# typewriter_shift.net
KiCad netlist of a schematic drawn in EAGLE
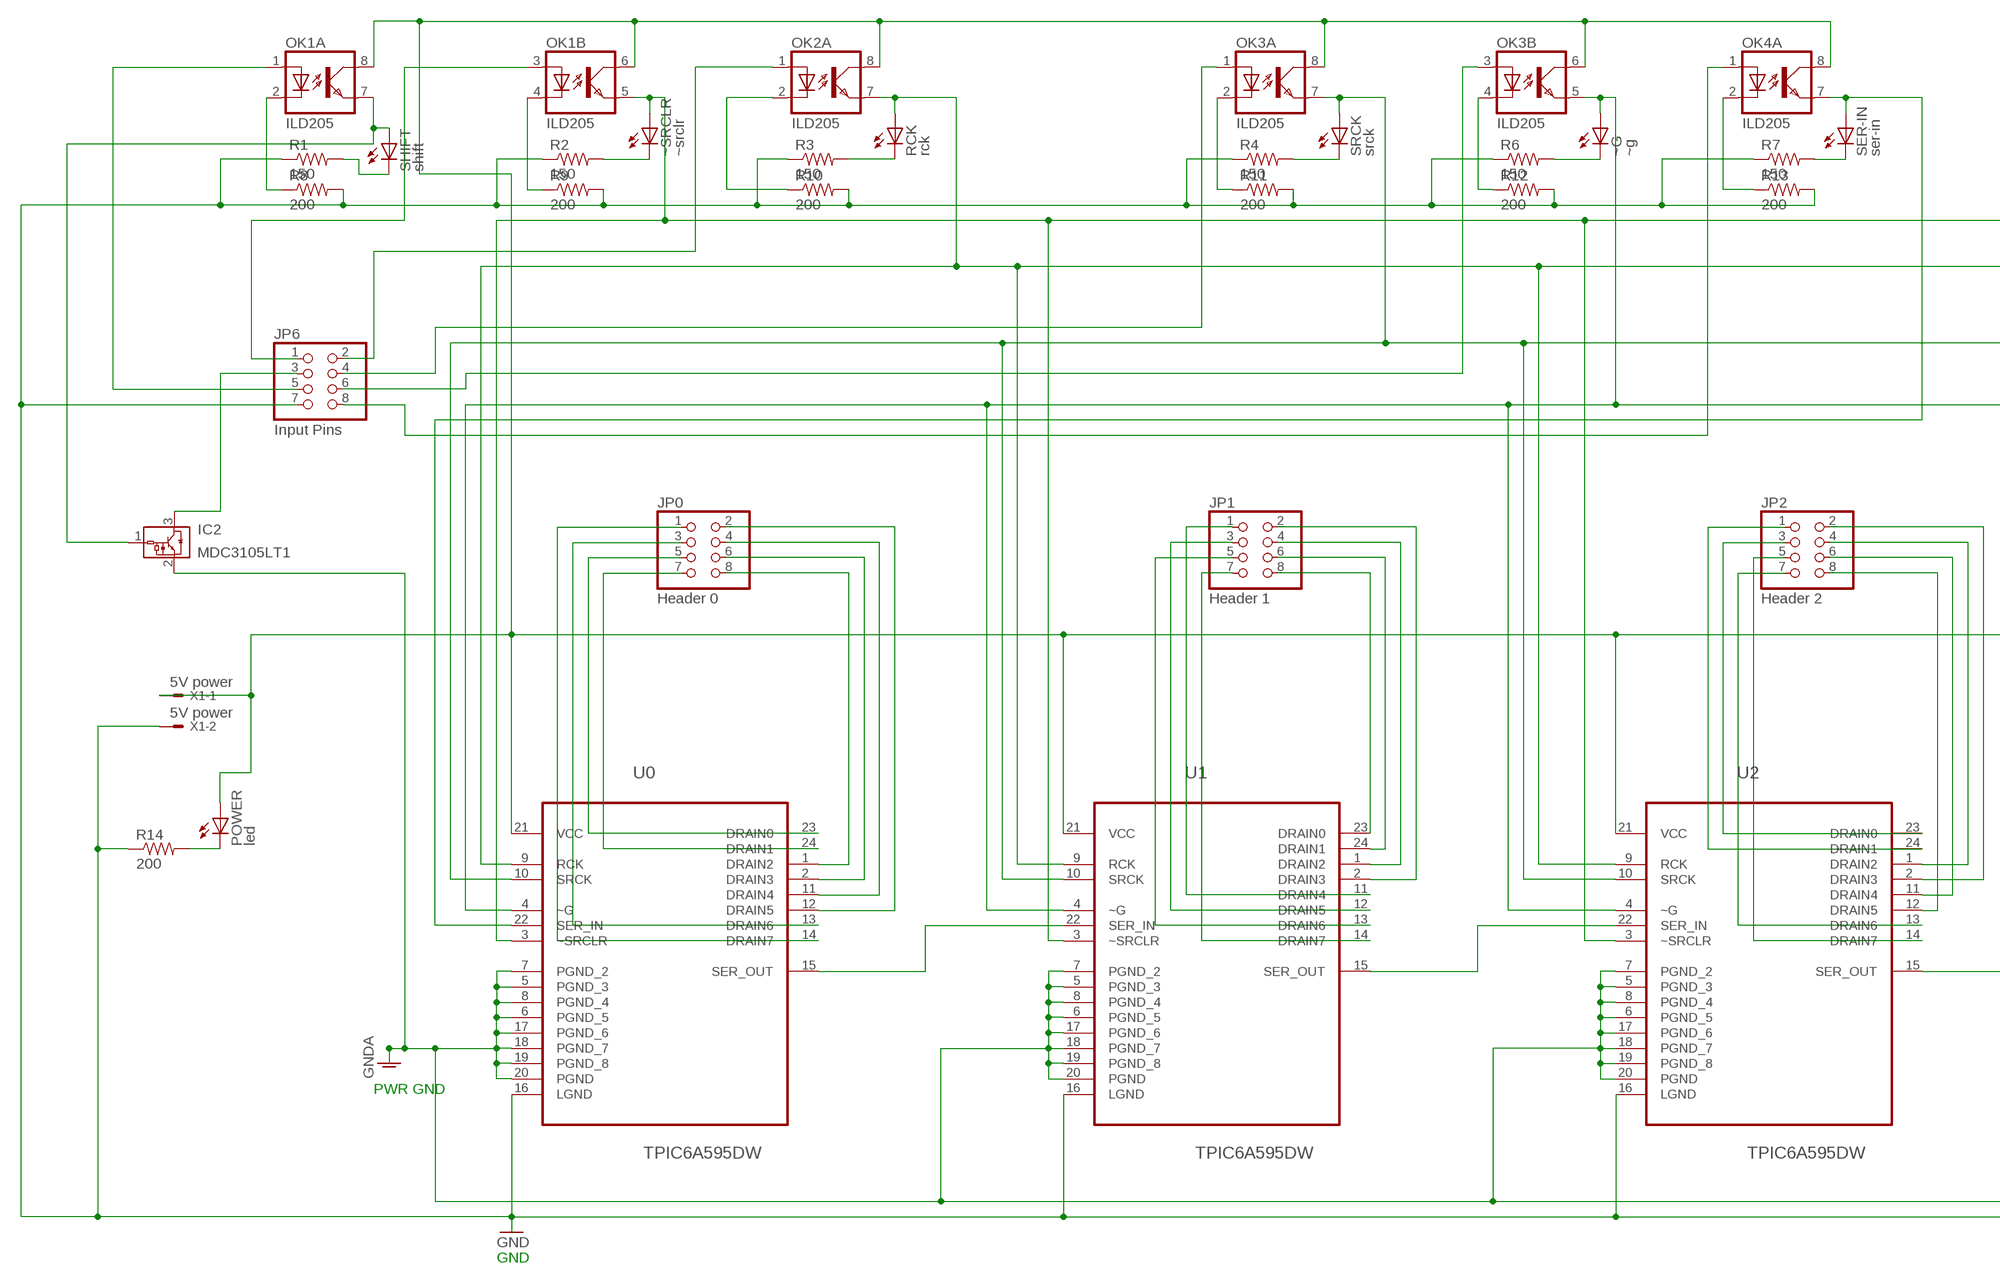
[diagram p0: schematic, sheet 1, part 1 of 2]
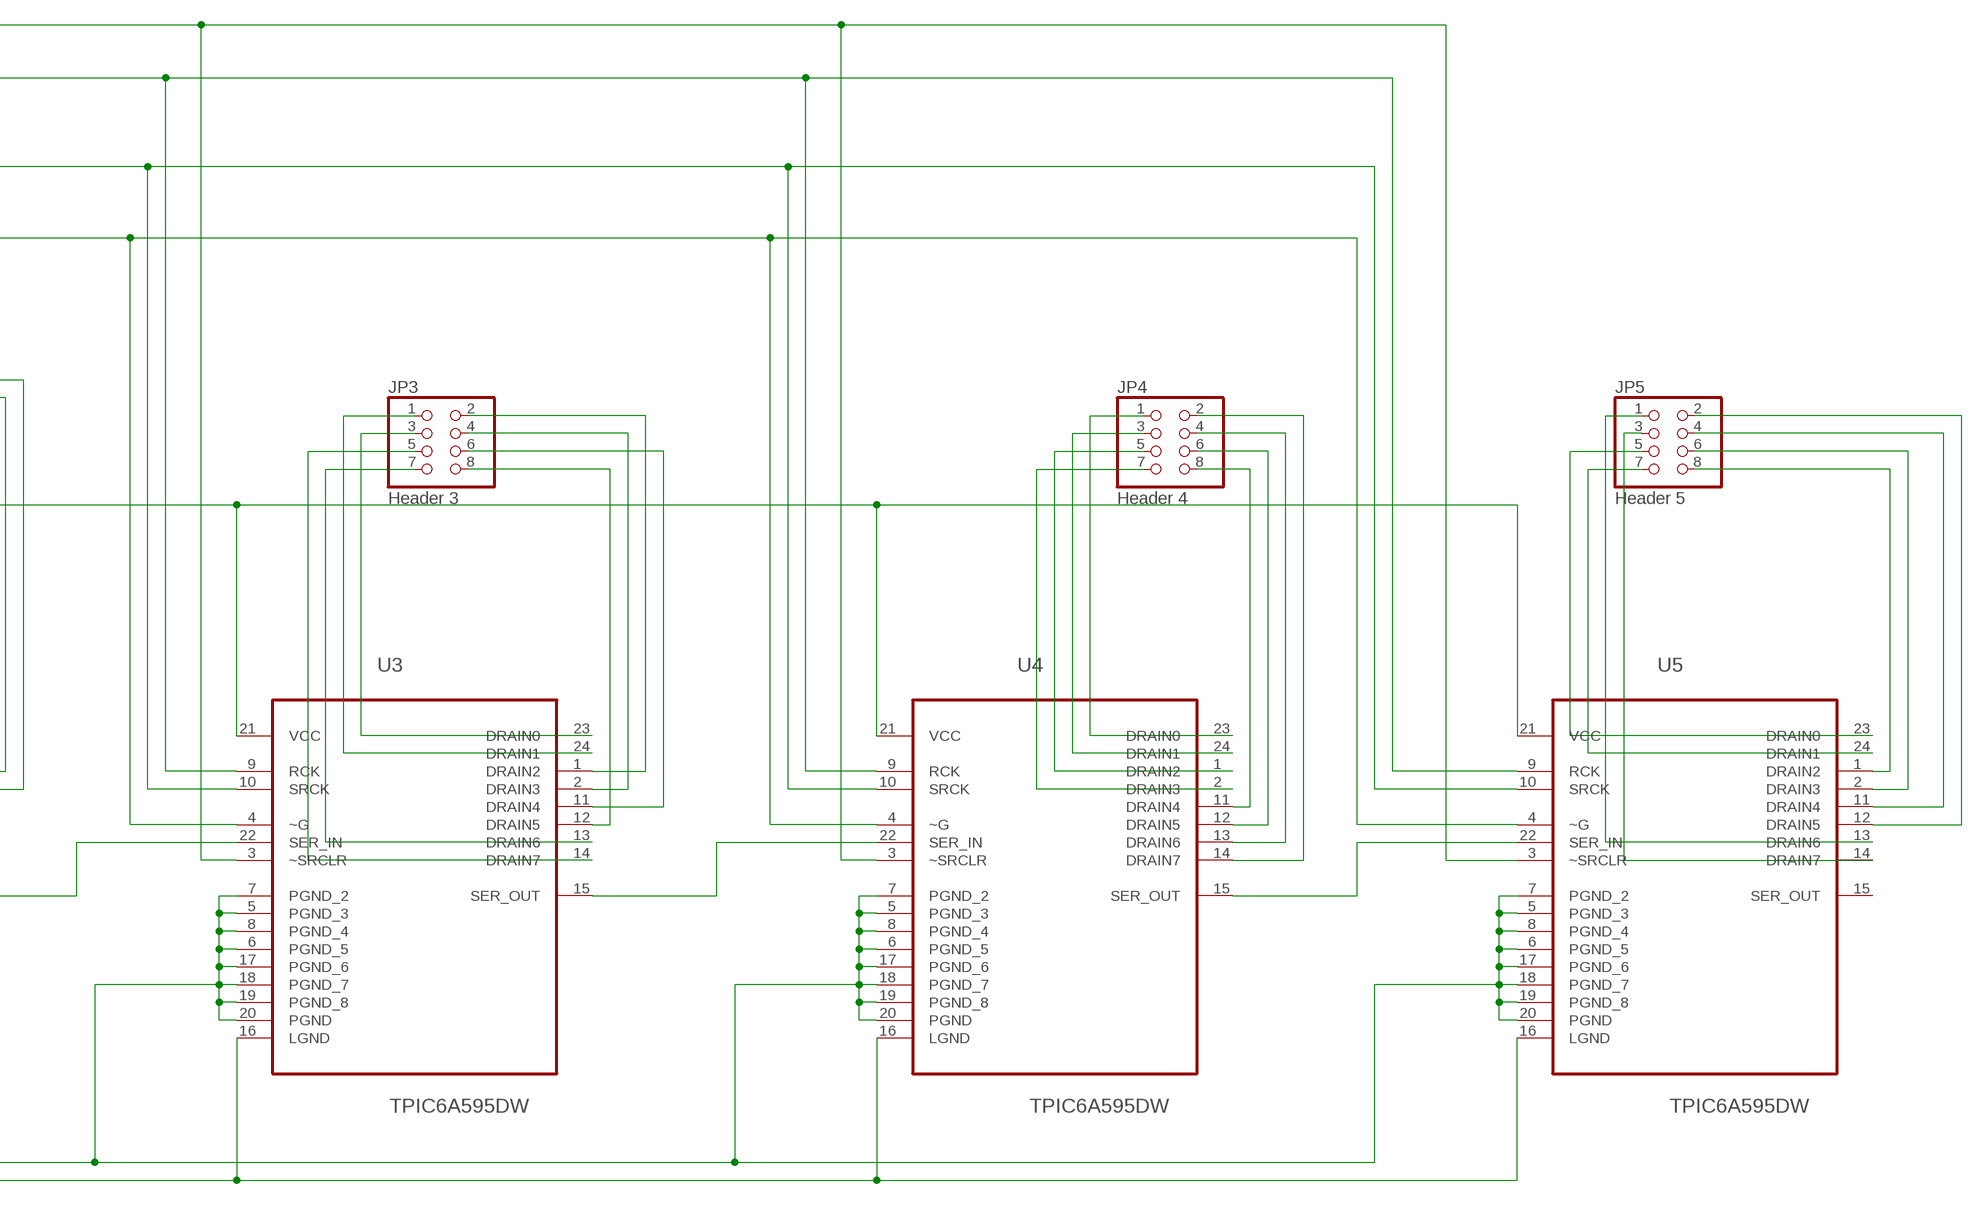
[diagram p1: schematic, sheet 1, part 2 of 2]

(export (version "E")
  (design (tool "Eeschema 10.0.6"))
  (components
    (comp (ref "IC2")
      (value "MDC3105LT1")
      (footprint "eagle-import:SOT23")
      (fields (field (name "MF") "ON SEMICONDUCTOR"))
      (libsource (lib "eagle-import") (part "MDC3105LT1"))
    )
    (comp (ref "JP0")
      (value "Header 0")
      (footprint "eagle-import:2X04_90")
      (libsource (lib "eagle-import") (part "PINHD-2X4/90"))
    )
    (comp (ref "JP1")
      (value "Header 1")
      (footprint "eagle-import:2X04_90")
      (libsource (lib "eagle-import") (part "PINHD-2X4/90"))
    )
    (comp (ref "JP2")
      (value "Header 2")
      (footprint "eagle-import:2X04_90")
      (libsource (lib "eagle-import") (part "PINHD-2X4/90"))
    )
    (comp (ref "JP3")
      (value "Header 3")
      (footprint "eagle-import:2X04_90")
      (libsource (lib "eagle-import") (part "PINHD-2X4/90"))
    )
    (comp (ref "JP4")
      (value "Header 4")
      (footprint "eagle-import:2X04_90")
      (libsource (lib "eagle-import") (part "PINHD-2X4/90"))
    )
    (comp (ref "JP5")
      (value "Header 5")
      (footprint "eagle-import:2X04_90")
      (libsource (lib "eagle-import") (part "PINHD-2X4/90"))
    )
    (comp (ref "JP6")
      (value "Input Pins")
      (footprint "eagle-import:2X04_90")
      (libsource (lib "eagle-import") (part "PINHD-2X4/90"))
    )
    (comp (ref "OK1")
      (value "ILD205")
      (footprint "eagle-import:SOIC08")
      (fields (field (name "MF") "VISHAY/TELEFUNKEN") (field (name "MPN") "ILD205T"))
      (libsource (lib "eagle-import") (part "ILD205"))
    )
    (comp (ref "OK2")
      (value "ILD205")
      (footprint "eagle-import:SOIC08")
      (fields (field (name "MF") "VISHAY/TELEFUNKEN") (field (name "MPN") "ILD205T"))
      (libsource (lib "eagle-import") (part "ILD205"))
    )
    (comp (ref "OK3")
      (value "ILD205")
      (footprint "eagle-import:SOIC08")
      (fields (field (name "MF") "VISHAY/TELEFUNKEN") (field (name "MPN") "ILD205T"))
      (libsource (lib "eagle-import") (part "ILD205"))
    )
    (comp (ref "OK4")
      (value "ILD205")
      (footprint "eagle-import:SOIC08")
      (fields (field (name "MF") "VISHAY/TELEFUNKEN") (field (name "MPN") "ILD205T"))
      (libsource (lib "eagle-import") (part "ILD205"))
    )
    (comp (ref "POWER")
      (value "led")
      (footprint "eagle-import:SML1206")
      (libsource (lib "eagle-import") (part "LEDSML1206"))
    )
    (comp (ref "R1")
      (value "150")
      (footprint "eagle-import:R1206")
      (libsource (lib "eagle-import") (part "R-US_R1206"))
    )
    (comp (ref "R2")
      (value "150")
      (footprint "eagle-import:R1206")
      (libsource (lib "eagle-import") (part "R-US_R1206"))
    )
    (comp (ref "R3")
      (value "150")
      (footprint "eagle-import:R1206")
      (libsource (lib "eagle-import") (part "R-US_R1206"))
    )
    (comp (ref "R4")
      (value "150")
      (footprint "eagle-import:R1206")
      (libsource (lib "eagle-import") (part "R-US_R1206"))
    )
    (comp (ref "R6")
      (value "150")
      (footprint "eagle-import:R1206")
      (libsource (lib "eagle-import") (part "R-US_R1206"))
    )
    (comp (ref "R7")
      (value "150")
      (footprint "eagle-import:R1206")
      (libsource (lib "eagle-import") (part "R-US_R1206"))
    )
    (comp (ref "R8")
      (value "200")
      (footprint "eagle-import:R1206")
      (libsource (lib "eagle-import") (part "R-US_R1206"))
    )
    (comp (ref "R9")
      (value "200")
      (footprint "eagle-import:R1206")
      (libsource (lib "eagle-import") (part "R-US_R1206"))
    )
    (comp (ref "R10")
      (value "200")
      (footprint "eagle-import:R1206")
      (libsource (lib "eagle-import") (part "R-US_R1206"))
    )
    (comp (ref "R11")
      (value "200")
      (footprint "eagle-import:R1206")
      (libsource (lib "eagle-import") (part "R-US_R1206"))
    )
    (comp (ref "R12")
      (value "200")
      (footprint "eagle-import:R1206")
      (libsource (lib "eagle-import") (part "R-US_R1206"))
    )
    (comp (ref "R13")
      (value "200")
      (footprint "eagle-import:R1206")
      (libsource (lib "eagle-import") (part "R-US_R1206"))
    )
    (comp (ref "R14")
      (value "200")
      (footprint "eagle-import:R1206")
      (libsource (lib "eagle-import") (part "R-US_R1206"))
    )
    (comp (ref "RCK")
      (value "rck")
      (footprint "eagle-import:SML1206")
      (libsource (lib "eagle-import") (part "LEDSML1206"))
    )
    (comp (ref "SER-IN")
      (value "ser-in")
      (footprint "eagle-import:SML1206")
      (libsource (lib "eagle-import") (part "LEDSML1206"))
    )
    (comp (ref "SHIFT")
      (value "shift")
      (footprint "eagle-import:SML1206")
      (libsource (lib "eagle-import") (part "LEDSML1206"))
    )
    (comp (ref "SRCK")
      (value "srck")
      (footprint "eagle-import:SML1206")
      (libsource (lib "eagle-import") (part "LEDSML1206"))
    )
    (comp (ref "U0")
      (value "TPIC6A595DW")
      (footprint "eagle-import:SOIC127P1030X265-24N")
      (libsource (lib "eagle-import") (part "TPIC6A595DW"))
    )
    (comp (ref "U1")
      (value "TPIC6A595DW")
      (footprint "eagle-import:SOIC127P1030X265-24N")
      (libsource (lib "eagle-import") (part "TPIC6A595DW"))
    )
    (comp (ref "U2")
      (value "TPIC6A595DW")
      (footprint "eagle-import:SOIC127P1030X265-24N")
      (libsource (lib "eagle-import") (part "TPIC6A595DW"))
    )
    (comp (ref "U3")
      (value "TPIC6A595DW")
      (footprint "eagle-import:SOIC127P1030X265-24N")
      (libsource (lib "eagle-import") (part "TPIC6A595DW"))
    )
    (comp (ref "U4")
      (value "TPIC6A595DW")
      (footprint "eagle-import:SOIC127P1030X265-24N")
      (libsource (lib "eagle-import") (part "TPIC6A595DW"))
    )
    (comp (ref "U5")
      (value "TPIC6A595DW")
      (footprint "eagle-import:SOIC127P1030X265-24N")
      (libsource (lib "eagle-import") (part "TPIC6A595DW"))
    )
    (comp (ref "X1")
      (value "5V power")
      (footprint "eagle-import:KK-156-2")
      (libsource (lib "eagle-import") (part "KK-156-2"))
    )
    (comp (ref "~G")
      (value "~g")
      (footprint "eagle-import:SML1206")
      (libsource (lib "eagle-import") (part "LEDSML1206"))
    )
    (comp (ref "~SRCLR")
      (value "~srclr")
      (footprint "eagle-import:SML1206")
      (libsource (lib "eagle-import") (part "LEDSML1206"))
    )
  )
  (nets
    (net (code "1") (name "GND") (class "Default")
      (node (ref "JP6") (pin "7") (pinfunction "7_7") (pintype "passive"))
      (node (ref "R1") (pin "1") (pinfunction "1_1") (pintype "passive"))
      (node (ref "R10") (pin "2") (pinfunction "2_2") (pintype "passive"))
      (node (ref "R11") (pin "2") (pinfunction "2_2") (pintype "passive"))
      (node (ref "R12") (pin "2") (pinfunction "2_2") (pintype "passive"))
      (node (ref "R13") (pin "2") (pinfunction "2_2") (pintype "passive"))
      (node (ref "R14") (pin "1") (pinfunction "1_1") (pintype "passive"))
      (node (ref "R2") (pin "1") (pinfunction "1_1") (pintype "passive"))
      (node (ref "R3") (pin "1") (pinfunction "1_1") (pintype "passive"))
      (node (ref "R4") (pin "1") (pinfunction "1_1") (pintype "passive"))
      (node (ref "R6") (pin "1") (pinfunction "1_1") (pintype "passive"))
      (node (ref "R7") (pin "1") (pinfunction "1_1") (pintype "passive"))
      (node (ref "R8") (pin "2") (pinfunction "2_2") (pintype "passive"))
      (node (ref "R9") (pin "2") (pinfunction "2_2") (pintype "passive"))
      (node (ref "U0") (pin "16") (pinfunction "LGND_16") (pintype "passive"))
      (node (ref "U1") (pin "16") (pinfunction "LGND_16") (pintype "passive"))
      (node (ref "U2") (pin "16") (pinfunction "LGND_16") (pintype "passive"))
      (node (ref "U3") (pin "16") (pinfunction "LGND_16") (pintype "passive"))
      (node (ref "U4") (pin "16") (pinfunction "LGND_16") (pintype "passive"))
      (node (ref "U5") (pin "16") (pinfunction "LGND_16") (pintype "passive"))
      (node (ref "X1") (pin "2") (pinfunction "S_2") (pintype "passive"))
    )
    (net (code "2") (name "GNDA") (class "Default")
      (node (ref "IC2") (pin "2") (pinfunction "GND_2") (pintype "passive"))
      (node (ref "U0") (pin "17") (pinfunction "PGND_6_17") (pintype "passive"))
      (node (ref "U0") (pin "18") (pinfunction "PGND_7_18") (pintype "passive"))
      (node (ref "U0") (pin "19") (pinfunction "PGND_8_19") (pintype "passive"))
      (node (ref "U0") (pin "20") (pinfunction "PGND_20") (pintype "passive"))
      (node (ref "U0") (pin "5") (pinfunction "PGND_3_5") (pintype "passive"))
      (node (ref "U0") (pin "6") (pinfunction "PGND_5_6") (pintype "passive"))
      (node (ref "U0") (pin "7") (pinfunction "PGND_2_7") (pintype "passive"))
      (node (ref "U0") (pin "8") (pinfunction "PGND_4_8") (pintype "passive"))
      (node (ref "U1") (pin "17") (pinfunction "PGND_6_17") (pintype "passive"))
      (node (ref "U1") (pin "18") (pinfunction "PGND_7_18") (pintype "passive"))
      (node (ref "U1") (pin "19") (pinfunction "PGND_8_19") (pintype "passive"))
      (node (ref "U1") (pin "20") (pinfunction "PGND_20") (pintype "passive"))
      (node (ref "U1") (pin "5") (pinfunction "PGND_3_5") (pintype "passive"))
      (node (ref "U1") (pin "6") (pinfunction "PGND_5_6") (pintype "passive"))
      (node (ref "U1") (pin "7") (pinfunction "PGND_2_7") (pintype "passive"))
      (node (ref "U1") (pin "8") (pinfunction "PGND_4_8") (pintype "passive"))
      (node (ref "U2") (pin "17") (pinfunction "PGND_6_17") (pintype "passive"))
      (node (ref "U2") (pin "18") (pinfunction "PGND_7_18") (pintype "passive"))
      (node (ref "U2") (pin "19") (pinfunction "PGND_8_19") (pintype "passive"))
      (node (ref "U2") (pin "20") (pinfunction "PGND_20") (pintype "passive"))
      (node (ref "U2") (pin "5") (pinfunction "PGND_3_5") (pintype "passive"))
      (node (ref "U2") (pin "6") (pinfunction "PGND_5_6") (pintype "passive"))
      (node (ref "U2") (pin "7") (pinfunction "PGND_2_7") (pintype "passive"))
      (node (ref "U2") (pin "8") (pinfunction "PGND_4_8") (pintype "passive"))
      (node (ref "U3") (pin "17") (pinfunction "PGND_6_17") (pintype "passive"))
      (node (ref "U3") (pin "18") (pinfunction "PGND_7_18") (pintype "passive"))
      (node (ref "U3") (pin "19") (pinfunction "PGND_8_19") (pintype "passive"))
      (node (ref "U3") (pin "20") (pinfunction "PGND_20") (pintype "passive"))
      (node (ref "U3") (pin "5") (pinfunction "PGND_3_5") (pintype "passive"))
      (node (ref "U3") (pin "6") (pinfunction "PGND_5_6") (pintype "passive"))
      (node (ref "U3") (pin "7") (pinfunction "PGND_2_7") (pintype "passive"))
      (node (ref "U3") (pin "8") (pinfunction "PGND_4_8") (pintype "passive"))
      (node (ref "U4") (pin "17") (pinfunction "PGND_6_17") (pintype "passive"))
      (node (ref "U4") (pin "18") (pinfunction "PGND_7_18") (pintype "passive"))
      (node (ref "U4") (pin "19") (pinfunction "PGND_8_19") (pintype "passive"))
      (node (ref "U4") (pin "20") (pinfunction "PGND_20") (pintype "passive"))
      (node (ref "U4") (pin "5") (pinfunction "PGND_3_5") (pintype "passive"))
      (node (ref "U4") (pin "6") (pinfunction "PGND_5_6") (pintype "passive"))
      (node (ref "U4") (pin "7") (pinfunction "PGND_2_7") (pintype "passive"))
      (node (ref "U4") (pin "8") (pinfunction "PGND_4_8") (pintype "passive"))
      (node (ref "U5") (pin "17") (pinfunction "PGND_6_17") (pintype "passive"))
      (node (ref "U5") (pin "18") (pinfunction "PGND_7_18") (pintype "passive"))
      (node (ref "U5") (pin "19") (pinfunction "PGND_8_19") (pintype "passive"))
      (node (ref "U5") (pin "20") (pinfunction "PGND_20") (pintype "passive"))
      (node (ref "U5") (pin "5") (pinfunction "PGND_3_5") (pintype "passive"))
      (node (ref "U5") (pin "6") (pinfunction "PGND_5_6") (pintype "passive"))
      (node (ref "U5") (pin "7") (pinfunction "PGND_2_7") (pintype "passive"))
      (node (ref "U5") (pin "8") (pinfunction "PGND_4_8") (pintype "passive"))
    )
    (net (code "3") (name "Net-(IC2-VIN)") (class "Default")
      (node (ref "IC2") (pin "1") (pinfunction "VIN_1") (pintype "passive"))
      (node (ref "OK1") (pin "7") (pinfunction "EMIT_7") (pintype "passive"))
      (node (ref "SHIFT") (pin "A") (pinfunction "A_A") (pintype "passive"))
    )
    (net (code "4") (name "Net-(IC2-VOUT)") (class "Default")
      (node (ref "IC2") (pin "3") (pinfunction "VOUT_3") (pintype "passive"))
      (node (ref "JP6") (pin "3") (pinfunction "3_3") (pintype "passive"))
    )
    (net (code "5") (name "Net-(OK1A-A)") (class "Default")
      (node (ref "JP6") (pin "5") (pinfunction "5_5") (pintype "passive"))
      (node (ref "OK1") (pin "1") (pinfunction "A_1") (pintype "passive"))
    )
    (net (code "6") (name "Net-(OK1A-C)") (class "Default")
      (node (ref "OK1") (pin "2") (pinfunction "C_2") (pintype "passive"))
      (node (ref "R8") (pin "1") (pinfunction "1_1") (pintype "passive"))
    )
    (net (code "7") (name "Net-(OK1A-COL)") (class "Default")
      (node (ref "OK1") (pin "6") (pinfunction "COL_6") (pintype "passive"))
      (node (ref "OK1") (pin "8") (pinfunction "COL_8") (pintype "passive"))
      (node (ref "OK2") (pin "8") (pinfunction "COL_8") (pintype "passive"))
      (node (ref "OK3") (pin "6") (pinfunction "COL_6") (pintype "passive"))
      (node (ref "OK3") (pin "8") (pinfunction "COL_8") (pintype "passive"))
      (node (ref "OK4") (pin "8") (pinfunction "COL_8") (pintype "passive"))
      (node (ref "POWER") (pin "A") (pinfunction "A_A") (pintype "passive"))
      (node (ref "U0") (pin "21") (pinfunction "VCC_21") (pintype "power_in"))
      (node (ref "U1") (pin "21") (pinfunction "VCC_21") (pintype "power_in"))
      (node (ref "U2") (pin "21") (pinfunction "VCC_21") (pintype "power_in"))
      (node (ref "U3") (pin "21") (pinfunction "VCC_21") (pintype "power_in"))
      (node (ref "U4") (pin "21") (pinfunction "VCC_21") (pintype "power_in"))
      (node (ref "U5") (pin "21") (pinfunction "VCC_21") (pintype "power_in"))
      (node (ref "X1") (pin "1") (pinfunction "S_1") (pintype "passive"))
    )
    (net (code "8") (name "Net-(OK1B-A)") (class "Default")
      (node (ref "JP6") (pin "1") (pinfunction "1_1") (pintype "passive"))
      (node (ref "OK1") (pin "3") (pinfunction "A_3") (pintype "passive"))
    )
    (net (code "9") (name "Net-(OK1B-C)") (class "Default")
      (node (ref "OK1") (pin "4") (pinfunction "C_4") (pintype "passive"))
      (node (ref "R9") (pin "1") (pinfunction "1_1") (pintype "passive"))
    )
    (net (code "10") (name "Net-(OK1B-EMIT)") (class "Default")
      (node (ref "OK1") (pin "5") (pinfunction "EMIT_5") (pintype "passive"))
      (node (ref "U0") (pin "3") (pinfunction "~{SRCLR}_3") (pintype "input"))
      (node (ref "U1") (pin "3") (pinfunction "~{SRCLR}_3") (pintype "input"))
      (node (ref "U2") (pin "3") (pinfunction "~{SRCLR}_3") (pintype "input"))
      (node (ref "U3") (pin "3") (pinfunction "~{SRCLR}_3") (pintype "input"))
      (node (ref "U4") (pin "3") (pinfunction "~{SRCLR}_3") (pintype "input"))
      (node (ref "U5") (pin "3") (pinfunction "~{SRCLR}_3") (pintype "input"))
      (node (ref "~SRCLR") (pin "A") (pinfunction "A_A") (pintype "passive"))
    )
    (net (code "11") (name "Net-(OK2A-A)") (class "Default")
      (node (ref "JP6") (pin "2") (pinfunction "2_2") (pintype "passive"))
      (node (ref "OK2") (pin "1") (pinfunction "A_1") (pintype "passive"))
    )
    (net (code "12") (name "Net-(OK2A-C)") (class "Default")
      (node (ref "OK2") (pin "2") (pinfunction "C_2") (pintype "passive"))
      (node (ref "R10") (pin "1") (pinfunction "1_1") (pintype "passive"))
    )
    (net (code "13") (name "Net-(OK2A-EMIT)") (class "Default")
      (node (ref "OK2") (pin "7") (pinfunction "EMIT_7") (pintype "passive"))
      (node (ref "RCK") (pin "A") (pinfunction "A_A") (pintype "passive"))
      (node (ref "U0") (pin "9") (pinfunction "RCK_9") (pintype "input"))
      (node (ref "U1") (pin "9") (pinfunction "RCK_9") (pintype "input"))
      (node (ref "U2") (pin "9") (pinfunction "RCK_9") (pintype "input"))
      (node (ref "U3") (pin "9") (pinfunction "RCK_9") (pintype "input"))
      (node (ref "U4") (pin "9") (pinfunction "RCK_9") (pintype "input"))
      (node (ref "U5") (pin "9") (pinfunction "RCK_9") (pintype "input"))
    )
    (net (code "14") (name "Net-(OK3A-A)") (class "Default")
      (node (ref "JP6") (pin "4") (pinfunction "4_4") (pintype "passive"))
      (node (ref "OK3") (pin "1") (pinfunction "A_1") (pintype "passive"))
    )
    (net (code "15") (name "Net-(OK3A-C)") (class "Default")
      (node (ref "OK3") (pin "2") (pinfunction "C_2") (pintype "passive"))
      (node (ref "R11") (pin "1") (pinfunction "1_1") (pintype "passive"))
    )
    (net (code "16") (name "Net-(OK3A-EMIT)") (class "Default")
      (node (ref "OK3") (pin "7") (pinfunction "EMIT_7") (pintype "passive"))
      (node (ref "SRCK") (pin "A") (pinfunction "A_A") (pintype "passive"))
      (node (ref "U0") (pin "10") (pinfunction "SRCK_10") (pintype "input"))
      (node (ref "U1") (pin "10") (pinfunction "SRCK_10") (pintype "input"))
      (node (ref "U2") (pin "10") (pinfunction "SRCK_10") (pintype "input"))
      (node (ref "U3") (pin "10") (pinfunction "SRCK_10") (pintype "input"))
      (node (ref "U4") (pin "10") (pinfunction "SRCK_10") (pintype "input"))
      (node (ref "U5") (pin "10") (pinfunction "SRCK_10") (pintype "input"))
    )
    (net (code "17") (name "Net-(OK3B-A)") (class "Default")
      (node (ref "JP6") (pin "6") (pinfunction "6_6") (pintype "passive"))
      (node (ref "OK3") (pin "3") (pinfunction "A_3") (pintype "passive"))
    )
    (net (code "18") (name "Net-(OK3B-C)") (class "Default")
      (node (ref "OK3") (pin "4") (pinfunction "C_4") (pintype "passive"))
      (node (ref "R12") (pin "1") (pinfunction "1_1") (pintype "passive"))
    )
    (net (code "19") (name "Net-(OK3B-EMIT)") (class "Default")
      (node (ref "OK3") (pin "5") (pinfunction "EMIT_5") (pintype "passive"))
      (node (ref "U0") (pin "4") (pinfunction "~{G}_4") (pintype "input"))
      (node (ref "U1") (pin "4") (pinfunction "~{G}_4") (pintype "input"))
      (node (ref "U2") (pin "4") (pinfunction "~{G}_4") (pintype "input"))
      (node (ref "U3") (pin "4") (pinfunction "~{G}_4") (pintype "input"))
      (node (ref "U4") (pin "4") (pinfunction "~{G}_4") (pintype "input"))
      (node (ref "U5") (pin "4") (pinfunction "~{G}_4") (pintype "input"))
      (node (ref "~G") (pin "A") (pinfunction "A_A") (pintype "passive"))
    )
    (net (code "20") (name "Net-(OK4A-A)") (class "Default")
      (node (ref "JP6") (pin "8") (pinfunction "8_8") (pintype "passive"))
      (node (ref "OK4") (pin "1") (pinfunction "A_1") (pintype "passive"))
    )
    (net (code "21") (name "Net-(OK4A-C)") (class "Default")
      (node (ref "OK4") (pin "2") (pinfunction "C_2") (pintype "passive"))
      (node (ref "R13") (pin "1") (pinfunction "1_1") (pintype "passive"))
    )
    (net (code "22") (name "Net-(OK4A-EMIT)") (class "Default")
      (node (ref "OK4") (pin "7") (pinfunction "EMIT_7") (pintype "passive"))
      (node (ref "SER-IN") (pin "A") (pinfunction "A_A") (pintype "passive"))
      (node (ref "U0") (pin "22") (pinfunction "SER_IN_22") (pintype "input"))
    )
    (net (code "23") (name "Net-(POWER-PadC)") (class "Default")
      (node (ref "POWER") (pin "C") (pinfunction "C_C") (pintype "passive"))
      (node (ref "R14") (pin "2") (pinfunction "2_2") (pintype "passive"))
    )
    (net (code "24") (name "Net-(R1-Pad2)") (class "Default")
      (node (ref "R1") (pin "2") (pinfunction "2_2") (pintype "passive"))
      (node (ref "SHIFT") (pin "C") (pinfunction "C_C") (pintype "passive"))
    )
    (net (code "25") (name "Net-(R2-Pad2)") (class "Default")
      (node (ref "R2") (pin "2") (pinfunction "2_2") (pintype "passive"))
      (node (ref "~SRCLR") (pin "C") (pinfunction "C_C") (pintype "passive"))
    )
    (net (code "26") (name "Net-(R3-Pad2)") (class "Default")
      (node (ref "R3") (pin "2") (pinfunction "2_2") (pintype "passive"))
      (node (ref "RCK") (pin "C") (pinfunction "C_C") (pintype "passive"))
    )
    (net (code "27") (name "Net-(R4-Pad2)") (class "Default")
      (node (ref "R4") (pin "2") (pinfunction "2_2") (pintype "passive"))
      (node (ref "SRCK") (pin "C") (pinfunction "C_C") (pintype "passive"))
    )
    (net (code "28") (name "Net-(R6-Pad2)") (class "Default")
      (node (ref "R6") (pin "2") (pinfunction "2_2") (pintype "passive"))
      (node (ref "~G") (pin "C") (pinfunction "C_C") (pintype "passive"))
    )
    (net (code "29") (name "Net-(R7-Pad2)") (class "Default")
      (node (ref "R7") (pin "2") (pinfunction "2_2") (pintype "passive"))
      (node (ref "SER-IN") (pin "C") (pinfunction "C_C") (pintype "passive"))
    )
    (net (code "30") (name "Net-(U0-DRAIN0)") (class "Default")
      (node (ref "JP0") (pin "5") (pinfunction "5_5") (pintype "passive"))
      (node (ref "U0") (pin "23") (pinfunction "DRAIN0_23") (pintype "output"))
    )
    (net (code "31") (name "Net-(U0-DRAIN1)") (class "Default")
      (node (ref "JP0") (pin "7") (pinfunction "7_7") (pintype "passive"))
      (node (ref "U0") (pin "24") (pinfunction "DRAIN1_24") (pintype "output"))
    )
    (net (code "32") (name "Net-(U0-DRAIN2)") (class "Default")
      (node (ref "JP0") (pin "8") (pinfunction "8_8") (pintype "passive"))
      (node (ref "U0") (pin "1") (pinfunction "DRAIN2_1") (pintype "output"))
    )
    (net (code "33") (name "Net-(U0-DRAIN3)") (class "Default")
      (node (ref "JP0") (pin "6") (pinfunction "6_6") (pintype "passive"))
      (node (ref "U0") (pin "2") (pinfunction "DRAIN3_2") (pintype "output"))
    )
    (net (code "34") (name "Net-(U0-DRAIN4)") (class "Default")
      (node (ref "JP0") (pin "4") (pinfunction "4_4") (pintype "passive"))
      (node (ref "U0") (pin "11") (pinfunction "DRAIN4_11") (pintype "output"))
    )
    (net (code "35") (name "Net-(U0-DRAIN5)") (class "Default")
      (node (ref "JP0") (pin "2") (pinfunction "2_2") (pintype "passive"))
      (node (ref "U0") (pin "12") (pinfunction "DRAIN5_12") (pintype "output"))
    )
    (net (code "36") (name "Net-(U0-DRAIN6)") (class "Default")
      (node (ref "JP0") (pin "3") (pinfunction "3_3") (pintype "passive"))
      (node (ref "U0") (pin "13") (pinfunction "DRAIN6_13") (pintype "output"))
    )
    (net (code "37") (name "Net-(U0-DRAIN7)") (class "Default")
      (node (ref "JP0") (pin "1") (pinfunction "1_1") (pintype "passive"))
      (node (ref "U0") (pin "14") (pinfunction "DRAIN7_14") (pintype "output"))
    )
    (net (code "38") (name "Net-(U0-SER_OUT)") (class "Default")
      (node (ref "U0") (pin "15") (pinfunction "SER_OUT_15") (pintype "output"))
      (node (ref "U1") (pin "22") (pinfunction "SER_IN_22") (pintype "input"))
    )
    (net (code "39") (name "Net-(U1-DRAIN0)") (class "Default")
      (node (ref "JP1") (pin "8") (pinfunction "8_8") (pintype "passive"))
      (node (ref "U1") (pin "23") (pinfunction "DRAIN0_23") (pintype "output"))
    )
    (net (code "40") (name "Net-(U1-DRAIN1)") (class "Default")
      (node (ref "JP1") (pin "6") (pinfunction "6_6") (pintype "passive"))
      (node (ref "U1") (pin "24") (pinfunction "DRAIN1_24") (pintype "output"))
    )
    (net (code "41") (name "Net-(U1-DRAIN2)") (class "Default")
      (node (ref "JP1") (pin "4") (pinfunction "4_4") (pintype "passive"))
      (node (ref "U1") (pin "1") (pinfunction "DRAIN2_1") (pintype "output"))
    )
    (net (code "42") (name "Net-(U1-DRAIN3)") (class "Default")
      (node (ref "JP1") (pin "2") (pinfunction "2_2") (pintype "passive"))
      (node (ref "U1") (pin "2") (pinfunction "DRAIN3_2") (pintype "output"))
    )
    (net (code "43") (name "Net-(U1-DRAIN4)") (class "Default")
      (node (ref "JP1") (pin "1") (pinfunction "1_1") (pintype "passive"))
      (node (ref "U1") (pin "11") (pinfunction "DRAIN4_11") (pintype "output"))
    )
    (net (code "44") (name "Net-(U1-DRAIN5)") (class "Default")
      (node (ref "JP1") (pin "3") (pinfunction "3_3") (pintype "passive"))
      (node (ref "U1") (pin "12") (pinfunction "DRAIN5_12") (pintype "output"))
    )
    (net (code "45") (name "Net-(U1-DRAIN6)") (class "Default")
      (node (ref "JP1") (pin "5") (pinfunction "5_5") (pintype "passive"))
      (node (ref "U1") (pin "13") (pinfunction "DRAIN6_13") (pintype "output"))
    )
    (net (code "46") (name "Net-(U1-DRAIN7)") (class "Default")
      (node (ref "JP1") (pin "7") (pinfunction "7_7") (pintype "passive"))
      (node (ref "U1") (pin "14") (pinfunction "DRAIN7_14") (pintype "output"))
    )
    (net (code "47") (name "Net-(U1-SER_OUT)") (class "Default")
      (node (ref "U1") (pin "15") (pinfunction "SER_OUT_15") (pintype "output"))
      (node (ref "U2") (pin "22") (pinfunction "SER_IN_22") (pintype "input"))
    )
    (net (code "48") (name "Net-(U2-DRAIN0)") (class "Default")
      (node (ref "JP2") (pin "3") (pinfunction "3_3") (pintype "passive"))
      (node (ref "U2") (pin "23") (pinfunction "DRAIN0_23") (pintype "output"))
    )
    (net (code "49") (name "Net-(U2-DRAIN1)") (class "Default")
      (node (ref "JP2") (pin "1") (pinfunction "1_1") (pintype "passive"))
      (node (ref "U2") (pin "24") (pinfunction "DRAIN1_24") (pintype "output"))
    )
    (net (code "50") (name "Net-(U2-DRAIN2)") (class "Default")
      (node (ref "JP2") (pin "4") (pinfunction "4_4") (pintype "passive"))
      (node (ref "U2") (pin "1") (pinfunction "DRAIN2_1") (pintype "output"))
    )
    (net (code "51") (name "Net-(U2-DRAIN3)") (class "Default")
      (node (ref "JP2") (pin "2") (pinfunction "2_2") (pintype "passive"))
      (node (ref "U2") (pin "2") (pinfunction "DRAIN3_2") (pintype "output"))
    )
    (net (code "52") (name "Net-(U2-DRAIN4)") (class "Default")
      (node (ref "JP2") (pin "6") (pinfunction "6_6") (pintype "passive"))
      (node (ref "U2") (pin "11") (pinfunction "DRAIN4_11") (pintype "output"))
    )
    (net (code "53") (name "Net-(U2-DRAIN5)") (class "Default")
      (node (ref "JP2") (pin "8") (pinfunction "8_8") (pintype "passive"))
      (node (ref "U2") (pin "12") (pinfunction "DRAIN5_12") (pintype "output"))
    )
    (net (code "54") (name "Net-(U2-DRAIN6)") (class "Default")
      (node (ref "JP2") (pin "7") (pinfunction "7_7") (pintype "passive"))
      (node (ref "U2") (pin "13") (pinfunction "DRAIN6_13") (pintype "output"))
    )
    (net (code "55") (name "Net-(U2-DRAIN7)") (class "Default")
      (node (ref "JP2") (pin "5") (pinfunction "5_5") (pintype "passive"))
      (node (ref "U2") (pin "14") (pinfunction "DRAIN7_14") (pintype "output"))
    )
    (net (code "56") (name "Net-(U2-SER_OUT)") (class "Default")
      (node (ref "U2") (pin "15") (pinfunction "SER_OUT_15") (pintype "output"))
      (node (ref "U3") (pin "22") (pinfunction "SER_IN_22") (pintype "input"))
    )
    (net (code "57") (name "Net-(U3-DRAIN0)") (class "Default")
      (node (ref "JP3") (pin "3") (pinfunction "3_3") (pintype "passive"))
      (node (ref "U3") (pin "23") (pinfunction "DRAIN0_23") (pintype "output"))
    )
    (net (code "58") (name "Net-(U3-DRAIN1)") (class "Default")
      (node (ref "JP3") (pin "1") (pinfunction "1_1") (pintype "passive"))
      (node (ref "U3") (pin "24") (pinfunction "DRAIN1_24") (pintype "output"))
    )
    (net (code "59") (name "Net-(U3-DRAIN2)") (class "Default")
      (node (ref "JP3") (pin "2") (pinfunction "2_2") (pintype "passive"))
      (node (ref "U3") (pin "1") (pinfunction "DRAIN2_1") (pintype "output"))
    )
    (net (code "60") (name "Net-(U3-DRAIN3)") (class "Default")
      (node (ref "JP3") (pin "4") (pinfunction "4_4") (pintype "passive"))
      (node (ref "U3") (pin "2") (pinfunction "DRAIN3_2") (pintype "output"))
    )
    (net (code "61") (name "Net-(U3-DRAIN4)") (class "Default")
      (node (ref "JP3") (pin "6") (pinfunction "6_6") (pintype "passive"))
      (node (ref "U3") (pin "11") (pinfunction "DRAIN4_11") (pintype "output"))
    )
    (net (code "62") (name "Net-(U3-DRAIN5)") (class "Default")
      (node (ref "JP3") (pin "8") (pinfunction "8_8") (pintype "passive"))
      (node (ref "U3") (pin "12") (pinfunction "DRAIN5_12") (pintype "output"))
    )
    (net (code "63") (name "Net-(U3-DRAIN6)") (class "Default")
      (node (ref "JP3") (pin "7") (pinfunction "7_7") (pintype "passive"))
      (node (ref "U3") (pin "13") (pinfunction "DRAIN6_13") (pintype "output"))
    )
    (net (code "64") (name "Net-(U3-DRAIN7)") (class "Default")
      (node (ref "JP3") (pin "5") (pinfunction "5_5") (pintype "passive"))
      (node (ref "U3") (pin "14") (pinfunction "DRAIN7_14") (pintype "output"))
    )
    (net (code "65") (name "Net-(U3-SER_OUT)") (class "Default")
      (node (ref "U3") (pin "15") (pinfunction "SER_OUT_15") (pintype "output"))
      (node (ref "U4") (pin "22") (pinfunction "SER_IN_22") (pintype "input"))
    )
    (net (code "66") (name "Net-(U4-DRAIN0)") (class "Default")
      (node (ref "JP4") (pin "1") (pinfunction "1_1") (pintype "passive"))
      (node (ref "U4") (pin "23") (pinfunction "DRAIN0_23") (pintype "output"))
    )
    (net (code "67") (name "Net-(U4-DRAIN1)") (class "Default")
      (node (ref "JP4") (pin "3") (pinfunction "3_3") (pintype "passive"))
      (node (ref "U4") (pin "24") (pinfunction "DRAIN1_24") (pintype "output"))
    )
    (net (code "68") (name "Net-(U4-DRAIN2)") (class "Default")
      (node (ref "JP4") (pin "5") (pinfunction "5_5") (pintype "passive"))
      (node (ref "U4") (pin "1") (pinfunction "DRAIN2_1") (pintype "output"))
    )
    (net (code "69") (name "Net-(U4-DRAIN3)") (class "Default")
      (node (ref "JP4") (pin "7") (pinfunction "7_7") (pintype "passive"))
      (node (ref "U4") (pin "2") (pinfunction "DRAIN3_2") (pintype "output"))
    )
    (net (code "70") (name "Net-(U4-DRAIN4)") (class "Default")
      (node (ref "JP4") (pin "8") (pinfunction "8_8") (pintype "passive"))
      (node (ref "U4") (pin "11") (pinfunction "DRAIN4_11") (pintype "output"))
    )
    (net (code "71") (name "Net-(U4-DRAIN5)") (class "Default")
      (node (ref "JP4") (pin "6") (pinfunction "6_6") (pintype "passive"))
      (node (ref "U4") (pin "12") (pinfunction "DRAIN5_12") (pintype "output"))
    )
    (net (code "72") (name "Net-(U4-DRAIN6)") (class "Default")
      (node (ref "JP4") (pin "4") (pinfunction "4_4") (pintype "passive"))
      (node (ref "U4") (pin "13") (pinfunction "DRAIN6_13") (pintype "output"))
    )
    (net (code "73") (name "Net-(U4-DRAIN7)") (class "Default")
      (node (ref "JP4") (pin "2") (pinfunction "2_2") (pintype "passive"))
      (node (ref "U4") (pin "14") (pinfunction "DRAIN7_14") (pintype "output"))
    )
    (net (code "74") (name "Net-(U4-SER_OUT)") (class "Default")
      (node (ref "U4") (pin "15") (pinfunction "SER_OUT_15") (pintype "output"))
      (node (ref "U5") (pin "22") (pinfunction "SER_IN_22") (pintype "input"))
    )
    (net (code "75") (name "Net-(U5-DRAIN0)") (class "Default")
      (node (ref "JP5") (pin "5") (pinfunction "5_5") (pintype "passive"))
      (node (ref "U5") (pin "23") (pinfunction "DRAIN0_23") (pintype "output"))
    )
    (net (code "76") (name "Net-(U5-DRAIN1)") (class "Default")
      (node (ref "JP5") (pin "7") (pinfunction "7_7") (pintype "passive"))
      (node (ref "U5") (pin "24") (pinfunction "DRAIN1_24") (pintype "output"))
    )
    (net (code "77") (name "Net-(U5-DRAIN2)") (class "Default")
      (node (ref "JP5") (pin "8") (pinfunction "8_8") (pintype "passive"))
      (node (ref "U5") (pin "1") (pinfunction "DRAIN2_1") (pintype "output"))
    )
    (net (code "78") (name "Net-(U5-DRAIN3)") (class "Default")
      (node (ref "JP5") (pin "6") (pinfunction "6_6") (pintype "passive"))
      (node (ref "U5") (pin "2") (pinfunction "DRAIN3_2") (pintype "output"))
    )
    (net (code "79") (name "Net-(U5-DRAIN4)") (class "Default")
      (node (ref "JP5") (pin "4") (pinfunction "4_4") (pintype "passive"))
      (node (ref "U5") (pin "11") (pinfunction "DRAIN4_11") (pintype "output"))
    )
    (net (code "80") (name "Net-(U5-DRAIN5)") (class "Default")
      (node (ref "JP5") (pin "2") (pinfunction "2_2") (pintype "passive"))
      (node (ref "U5") (pin "12") (pinfunction "DRAIN5_12") (pintype "output"))
    )
    (net (code "81") (name "Net-(U5-DRAIN6)") (class "Default")
      (node (ref "JP5") (pin "1") (pinfunction "1_1") (pintype "passive"))
      (node (ref "U5") (pin "13") (pinfunction "DRAIN6_13") (pintype "output"))
    )
    (net (code "82") (name "Net-(U5-DRAIN7)") (class "Default")
      (node (ref "JP5") (pin "3") (pinfunction "3_3") (pintype "passive"))
      (node (ref "U5") (pin "14") (pinfunction "DRAIN7_14") (pintype "output"))
    )
    (net (code "83") (name "unconnected-(U5-SER_OUT-Pad15)") (class "Default")
      (node (ref "U5") (pin "15") (pinfunction "SER_OUT_15") (pintype "output"))
    )
  )
)
